# Sch_v3.net
KiCad netlist of a schematic drawn in EAGLE
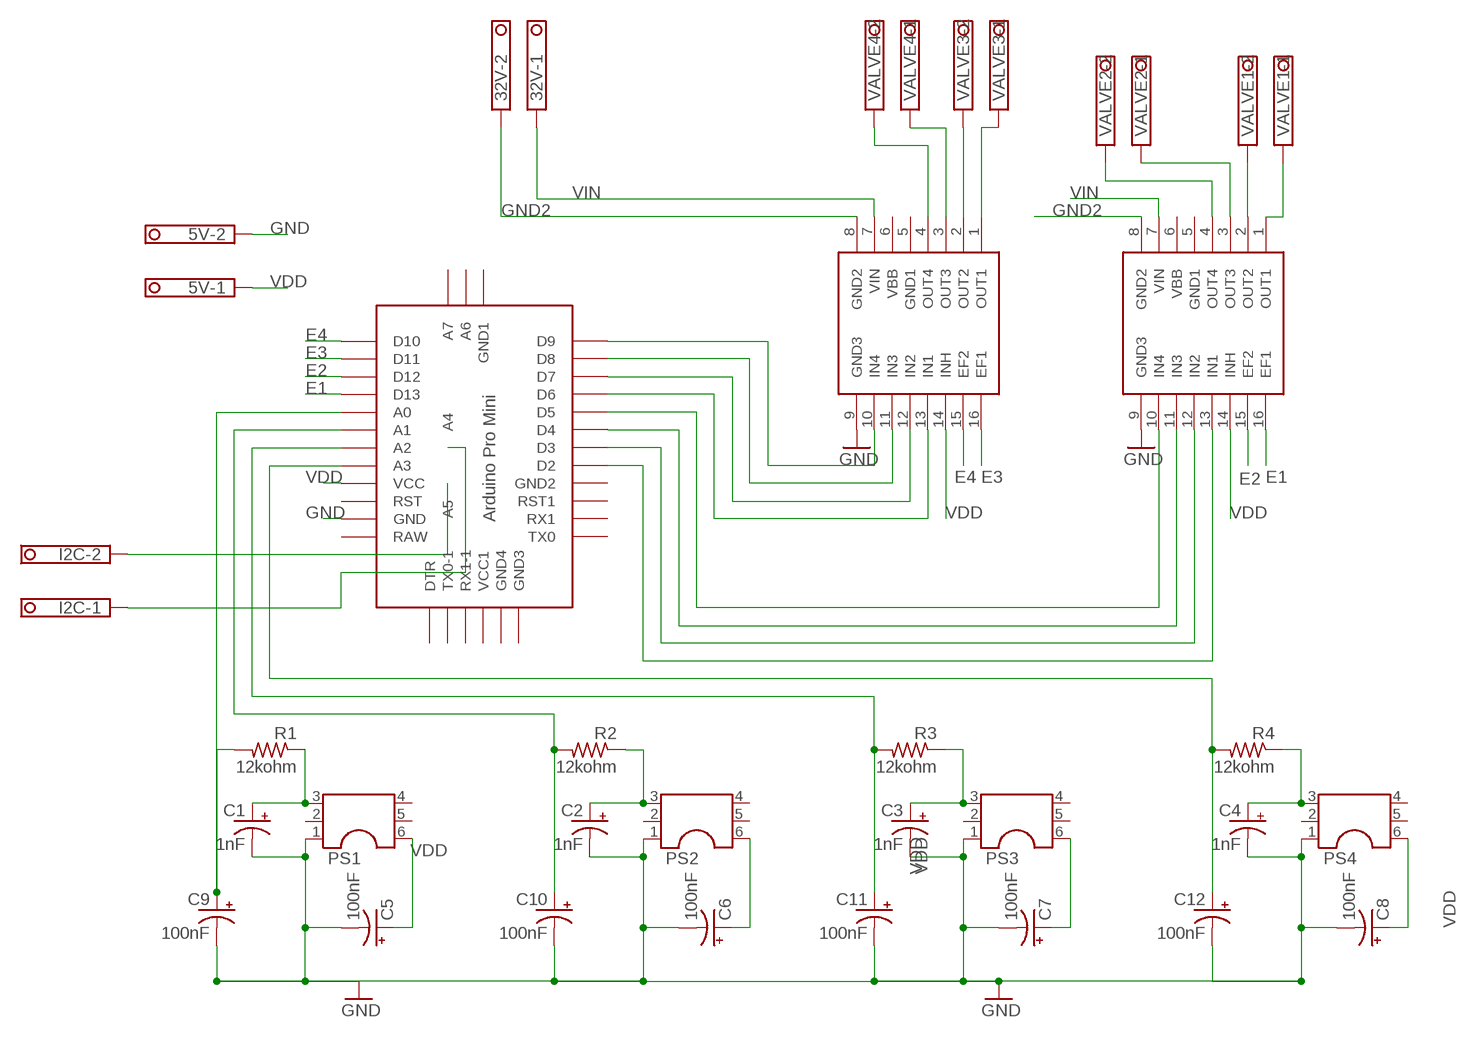
[diagram p0: schematic, sheet 1]

(export (version "E")
  (design (tool "Eeschema 10.0.6"))
  (components
    (comp (ref "5V")
      (value "1751248")
      (footprint "eagle-import:1751248")
      (libsource (lib "eagle-import") (part "1751248"))
    )
    (comp (ref "32V")
      (value "1751248")
      (footprint "eagle-import:1751248")
      (libsource (lib "eagle-import") (part "1751248"))
    )
    (comp (ref "C1")
      (value "1nF")
      (footprint "eagle-import:E2,5-5")
      (libsource (lib "eagle-import") (part "CPOL-USE2.5-5"))
    )
    (comp (ref "C2")
      (value "1nF")
      (footprint "eagle-import:E2,5-5")
      (libsource (lib "eagle-import") (part "CPOL-USE2.5-5"))
    )
    (comp (ref "C3")
      (value "1nF")
      (footprint "eagle-import:E2,5-5")
      (libsource (lib "eagle-import") (part "CPOL-USE2.5-5"))
    )
    (comp (ref "C4")
      (value "1nF")
      (footprint "eagle-import:E2,5-5")
      (libsource (lib "eagle-import") (part "CPOL-USE2.5-5"))
    )
    (comp (ref "C5")
      (value "100nF")
      (footprint "eagle-import:E2,5-5")
      (libsource (lib "eagle-import") (part "CPOL-USE2.5-5"))
    )
    (comp (ref "C6")
      (value "100nF")
      (footprint "eagle-import:E2,5-5")
      (libsource (lib "eagle-import") (part "CPOL-USE2.5-5"))
    )
    (comp (ref "C7")
      (value "100nF")
      (footprint "eagle-import:E2,5-5")
      (libsource (lib "eagle-import") (part "CPOL-USE2.5-5"))
    )
    (comp (ref "C8")
      (value "100nF")
      (footprint "eagle-import:E2,5-5")
      (libsource (lib "eagle-import") (part "CPOL-USE2.5-5"))
    )
    (comp (ref "C9")
      (value "100nF")
      (footprint "eagle-import:E2,5-5")
      (libsource (lib "eagle-import") (part "CPOL-USE2.5-5"))
    )
    (comp (ref "C10")
      (value "100nF")
      (footprint "eagle-import:E2,5-5")
      (libsource (lib "eagle-import") (part "CPOL-USE2.5-5"))
    )
    (comp (ref "C11")
      (value "100nF")
      (footprint "eagle-import:E2,5-5")
      (libsource (lib "eagle-import") (part "CPOL-USE2.5-5"))
    )
    (comp (ref "C12")
      (value "100nF")
      (footprint "eagle-import:E2,5-5")
      (libsource (lib "eagle-import") (part "CPOL-USE2.5-5"))
    )
    (comp (ref "I2C")
      (value "1751248")
      (footprint "eagle-import:1751248")
      (libsource (lib "eagle-import") (part "1751248"))
    )
    (comp (ref "PS1")
      (value "DIL6")
      (footprint "eagle-import:DIL06")
      (libsource (lib "eagle-import") (part "DIL6"))
    )
    (comp (ref "PS2")
      (value "DIL6")
      (footprint "eagle-import:DIL06")
      (libsource (lib "eagle-import") (part "DIL6"))
    )
    (comp (ref "PS3")
      (value "DIL6")
      (footprint "eagle-import:DIL06")
      (libsource (lib "eagle-import") (part "DIL6"))
    )
    (comp (ref "PS4")
      (value "DIL6")
      (footprint "eagle-import:DIL06")
      (libsource (lib "eagle-import") (part "DIL6"))
    )
    (comp (ref "R1")
      (value "12kohm")
      (footprint "eagle-import:0204_7")
      (libsource (lib "eagle-import") (part "R-US_0204/7"))
    )
    (comp (ref "R2")
      (value "12kohm")
      (footprint "eagle-import:0204_7")
      (libsource (lib "eagle-import") (part "R-US_0204/7"))
    )
    (comp (ref "R3")
      (value "12kohm")
      (footprint "eagle-import:0204_7")
      (libsource (lib "eagle-import") (part "R-US_0204/7"))
    )
    (comp (ref "R4")
      (value "12kohm")
      (footprint "eagle-import:0204_7")
      (libsource (lib "eagle-import") (part "R-US_0204/7"))
    )
    (comp (ref "U$1")
      (value "ABK-PRO-MINI")
      (footprint "eagle-import:ABK-PRO-MINI")
      (libsource (lib "eagle-import") (part "ABK-PRO-MINI"))
    )
    (comp (ref "U$2")
      (value "A4990")
      (footprint "eagle-import:A4990")
      (libsource (lib "eagle-import") (part "A4990"))
    )
    (comp (ref "U$3")
      (value "A4990")
      (footprint "eagle-import:A4990")
      (libsource (lib "eagle-import") (part "A4990"))
    )
    (comp (ref "VALVE1")
      (value "1751248")
      (footprint "eagle-import:1751248")
      (libsource (lib "eagle-import") (part "1751248"))
    )
    (comp (ref "VALVE2")
      (value "1751248")
      (footprint "eagle-import:1751248")
      (libsource (lib "eagle-import") (part "1751248"))
    )
    (comp (ref "VALVE3")
      (value "1751248")
      (footprint "eagle-import:1751248")
      (libsource (lib "eagle-import") (part "1751248"))
    )
    (comp (ref "VALVE4")
      (value "1751248")
      (footprint "eagle-import:1751248")
      (libsource (lib "eagle-import") (part "1751248"))
    )
  )
  (nets
    (net (code "1") (name "/E1") (class "Default")
      (node (ref "U$1") (pin "D13") (pinfunction "D13_D13") (pintype "bidirectional"))
      (node (ref "U$3") (pin "16") (pinfunction "EF1_16") (pintype "bidirectional"))
    )
    (net (code "2") (name "/E2") (class "Default")
      (node (ref "U$1") (pin "D12") (pinfunction "D12_D12") (pintype "bidirectional"))
      (node (ref "U$3") (pin "15") (pinfunction "EF2_15") (pintype "bidirectional"))
    )
    (net (code "3") (name "/E3") (class "Default")
      (node (ref "U$1") (pin "D11") (pinfunction "D11_D11") (pintype "bidirectional"))
      (node (ref "U$2") (pin "16") (pinfunction "EF1_16") (pintype "bidirectional"))
    )
    (net (code "4") (name "/E4") (class "Default")
      (node (ref "U$1") (pin "D10") (pinfunction "D10_D10") (pintype "bidirectional"))
      (node (ref "U$2") (pin "15") (pinfunction "EF2_15") (pintype "bidirectional"))
    )
    (net (code "5") (name "/GND2") (class "Default")
      (node (ref "32V") (pin "2") (pinfunction "K_2") (pintype "passive"))
      (node (ref "U$2") (pin "8") (pinfunction "GND2_8") (pintype "bidirectional"))
      (node (ref "U$3") (pin "8") (pinfunction "GND2_8") (pintype "bidirectional"))
    )
    (net (code "6") (name "/VDD") (class "Default")
      (node (ref "5V") (pin "1") (pinfunction "K_1") (pintype "passive"))
      (node (ref "C5") (pin "+") (pinfunction "+_+") (pintype "passive"))
      (node (ref "C6") (pin "+") (pinfunction "+_+") (pintype "passive"))
      (node (ref "C7") (pin "+") (pinfunction "+_+") (pintype "passive"))
      (node (ref "C8") (pin "+") (pinfunction "+_+") (pintype "passive"))
      (node (ref "PS1") (pin "6") (pinfunction "6_6") (pintype "passive"))
      (node (ref "PS2") (pin "6") (pinfunction "6_6") (pintype "passive"))
      (node (ref "PS3") (pin "6") (pinfunction "6_6") (pintype "passive"))
      (node (ref "PS4") (pin "6") (pinfunction "6_6") (pintype "passive"))
      (node (ref "U$1") (pin "VCC") (pinfunction "VCC_VCC") (pintype "bidirectional"))
      (node (ref "U$2") (pin "14") (pinfunction "INH_14") (pintype "bidirectional"))
      (node (ref "U$3") (pin "14") (pinfunction "INH_14") (pintype "bidirectional"))
    )
    (net (code "7") (name "/VIN") (class "Default")
      (node (ref "32V") (pin "1") (pinfunction "K_1") (pintype "passive"))
      (node (ref "U$2") (pin "7") (pinfunction "VIN_7") (pintype "bidirectional"))
      (node (ref "U$3") (pin "7") (pinfunction "VIN_7") (pintype "bidirectional"))
    )
    (net (code "8") (name "GND") (class "Default")
      (node (ref "5V") (pin "2") (pinfunction "K_2") (pintype "passive"))
      (node (ref "C1") (pin "-") (pinfunction "-_-") (pintype "passive"))
      (node (ref "C10") (pin "-") (pinfunction "-_-") (pintype "passive"))
      (node (ref "C11") (pin "-") (pinfunction "-_-") (pintype "passive"))
      (node (ref "C12") (pin "-") (pinfunction "-_-") (pintype "passive"))
      (node (ref "C2") (pin "-") (pinfunction "-_-") (pintype "passive"))
      (node (ref "C3") (pin "-") (pinfunction "-_-") (pintype "passive"))
      (node (ref "C4") (pin "-") (pinfunction "-_-") (pintype "passive"))
      (node (ref "C5") (pin "-") (pinfunction "-_-") (pintype "passive"))
      (node (ref "C6") (pin "-") (pinfunction "-_-") (pintype "passive"))
      (node (ref "C7") (pin "-") (pinfunction "-_-") (pintype "passive"))
      (node (ref "C8") (pin "-") (pinfunction "-_-") (pintype "passive"))
      (node (ref "C9") (pin "-") (pinfunction "-_-") (pintype "passive"))
      (node (ref "PS1") (pin "1") (pinfunction "1_1") (pintype "passive"))
      (node (ref "PS2") (pin "1") (pinfunction "1_1") (pintype "passive"))
      (node (ref "PS3") (pin "1") (pinfunction "1_1") (pintype "passive"))
      (node (ref "PS4") (pin "1") (pinfunction "1_1") (pintype "passive"))
      (node (ref "U$1") (pin "GND") (pinfunction "GND_GND") (pintype "bidirectional"))
      (node (ref "U$2") (pin "9") (pinfunction "GND3_9") (pintype "bidirectional"))
      (node (ref "U$3") (pin "9") (pinfunction "GND3_9") (pintype "bidirectional"))
    )
    (net (code "9") (name "Net-(C1-Pad+)") (class "Default")
      (node (ref "C1") (pin "+") (pinfunction "+_+") (pintype "passive"))
      (node (ref "PS1") (pin "3") (pinfunction "3_3") (pintype "passive"))
      (node (ref "R1") (pin "1") (pinfunction "1_1") (pintype "passive"))
    )
    (net (code "10") (name "Net-(C2-Pad+)") (class "Default")
      (node (ref "C2") (pin "+") (pinfunction "+_+") (pintype "passive"))
      (node (ref "PS2") (pin "3") (pinfunction "3_3") (pintype "passive"))
      (node (ref "R2") (pin "1") (pinfunction "1_1") (pintype "passive"))
    )
    (net (code "11") (name "Net-(C3-Pad+)") (class "Default")
      (node (ref "C3") (pin "+") (pinfunction "+_+") (pintype "passive"))
      (node (ref "PS3") (pin "3") (pinfunction "3_3") (pintype "passive"))
      (node (ref "R3") (pin "1") (pinfunction "1_1") (pintype "passive"))
    )
    (net (code "12") (name "Net-(C4-Pad+)") (class "Default")
      (node (ref "C4") (pin "+") (pinfunction "+_+") (pintype "passive"))
      (node (ref "PS4") (pin "3") (pinfunction "3_3") (pintype "passive"))
      (node (ref "R4") (pin "1") (pinfunction "1_1") (pintype "passive"))
    )
    (net (code "13") (name "Net-(C9-Pad+)") (class "Default")
      (node (ref "C9") (pin "+") (pinfunction "+_+") (pintype "passive"))
      (node (ref "R1") (pin "2") (pinfunction "2_2") (pintype "passive"))
      (node (ref "U$1") (pin "A0") (pinfunction "A0_A0") (pintype "bidirectional"))
    )
    (net (code "14") (name "Net-(C10-Pad+)") (class "Default")
      (node (ref "C10") (pin "+") (pinfunction "+_+") (pintype "passive"))
      (node (ref "R2") (pin "2") (pinfunction "2_2") (pintype "passive"))
      (node (ref "U$1") (pin "A1") (pinfunction "A1_A1") (pintype "bidirectional"))
    )
    (net (code "15") (name "Net-(C11-Pad+)") (class "Default")
      (node (ref "C11") (pin "+") (pinfunction "+_+") (pintype "passive"))
      (node (ref "R3") (pin "2") (pinfunction "2_2") (pintype "passive"))
      (node (ref "U$1") (pin "A2") (pinfunction "A2_A2") (pintype "bidirectional"))
    )
    (net (code "16") (name "Net-(C12-Pad+)") (class "Default")
      (node (ref "C12") (pin "+") (pinfunction "+_+") (pintype "passive"))
      (node (ref "R4") (pin "2") (pinfunction "2_2") (pintype "passive"))
      (node (ref "U$1") (pin "A3") (pinfunction "A3_A3") (pintype "bidirectional"))
    )
    (net (code "17") (name "Net-(I2CA-K)") (class "Default")
      (node (ref "I2C") (pin "1") (pinfunction "K_1") (pintype "passive"))
      (node (ref "U$1") (pin "A4") (pinfunction "A4_A4") (pintype "bidirectional"))
    )
    (net (code "18") (name "Net-(I2CB-K)") (class "Default")
      (node (ref "I2C") (pin "2") (pinfunction "K_2") (pintype "passive"))
      (node (ref "U$1") (pin "A5") (pinfunction "A5_A5") (pintype "bidirectional"))
    )
    (net (code "19") (name "Net-(U$2-IN1)") (class "Default")
      (node (ref "U$1") (pin "D6") (pinfunction "D6_D6") (pintype "bidirectional"))
      (node (ref "U$2") (pin "13") (pinfunction "IN1_13") (pintype "bidirectional"))
    )
    (net (code "20") (name "Net-(U$2-IN2)") (class "Default")
      (node (ref "U$1") (pin "D7") (pinfunction "D7_D7") (pintype "bidirectional"))
      (node (ref "U$2") (pin "12") (pinfunction "IN2_12") (pintype "bidirectional"))
    )
    (net (code "21") (name "Net-(U$2-IN3)") (class "Default")
      (node (ref "U$1") (pin "D8") (pinfunction "D8_D8") (pintype "bidirectional"))
      (node (ref "U$2") (pin "11") (pinfunction "IN3_11") (pintype "bidirectional"))
    )
    (net (code "22") (name "Net-(U$2-IN4)") (class "Default")
      (node (ref "U$1") (pin "D9") (pinfunction "D9_D9") (pintype "bidirectional"))
      (node (ref "U$2") (pin "10") (pinfunction "IN4_10") (pintype "bidirectional"))
    )
    (net (code "23") (name "Net-(U$2-OUT1)") (class "Default")
      (node (ref "U$2") (pin "1") (pinfunction "OUT1_1") (pintype "bidirectional"))
      (node (ref "VALVE3") (pin "1") (pinfunction "K_1") (pintype "passive"))
    )
    (net (code "24") (name "Net-(U$2-OUT2)") (class "Default")
      (node (ref "U$2") (pin "2") (pinfunction "OUT2_2") (pintype "bidirectional"))
      (node (ref "VALVE3") (pin "2") (pinfunction "K_2") (pintype "passive"))
    )
    (net (code "25") (name "Net-(U$2-OUT3)") (class "Default")
      (node (ref "U$2") (pin "3") (pinfunction "OUT3_3") (pintype "bidirectional"))
      (node (ref "VALVE4") (pin "1") (pinfunction "K_1") (pintype "passive"))
    )
    (net (code "26") (name "Net-(U$2-OUT4)") (class "Default")
      (node (ref "U$2") (pin "4") (pinfunction "OUT4_4") (pintype "bidirectional"))
      (node (ref "VALVE4") (pin "2") (pinfunction "K_2") (pintype "passive"))
    )
    (net (code "27") (name "Net-(U$3-IN1)") (class "Default")
      (node (ref "U$1") (pin "D2") (pinfunction "D2_D2") (pintype "bidirectional"))
      (node (ref "U$3") (pin "13") (pinfunction "IN1_13") (pintype "bidirectional"))
    )
    (net (code "28") (name "Net-(U$3-IN2)") (class "Default")
      (node (ref "U$1") (pin "D3") (pinfunction "D3_D3") (pintype "bidirectional"))
      (node (ref "U$3") (pin "12") (pinfunction "IN2_12") (pintype "bidirectional"))
    )
    (net (code "29") (name "Net-(U$3-IN3)") (class "Default")
      (node (ref "U$1") (pin "D4") (pinfunction "D4_D4") (pintype "bidirectional"))
      (node (ref "U$3") (pin "11") (pinfunction "IN3_11") (pintype "bidirectional"))
    )
    (net (code "30") (name "Net-(U$3-IN4)") (class "Default")
      (node (ref "U$1") (pin "D5") (pinfunction "D5_D5") (pintype "bidirectional"))
      (node (ref "U$3") (pin "10") (pinfunction "IN4_10") (pintype "bidirectional"))
    )
    (net (code "31") (name "Net-(U$3-OUT1)") (class "Default")
      (node (ref "U$3") (pin "1") (pinfunction "OUT1_1") (pintype "bidirectional"))
      (node (ref "VALVE1") (pin "1") (pinfunction "K_1") (pintype "passive"))
    )
    (net (code "32") (name "Net-(U$3-OUT2)") (class "Default")
      (node (ref "U$3") (pin "2") (pinfunction "OUT2_2") (pintype "bidirectional"))
      (node (ref "VALVE1") (pin "2") (pinfunction "K_2") (pintype "passive"))
    )
    (net (code "33") (name "Net-(U$3-OUT3)") (class "Default")
      (node (ref "U$3") (pin "3") (pinfunction "OUT3_3") (pintype "bidirectional"))
      (node (ref "VALVE2") (pin "1") (pinfunction "K_1") (pintype "passive"))
    )
    (net (code "34") (name "Net-(U$3-OUT4)") (class "Default")
      (node (ref "U$3") (pin "4") (pinfunction "OUT4_4") (pintype "bidirectional"))
      (node (ref "VALVE2") (pin "2") (pinfunction "K_2") (pintype "passive"))
    )
    (net (code "35") (name "unconnected-(PS1-Pad2)") (class "Default")
      (node (ref "PS1") (pin "2") (pinfunction "2_2") (pintype "passive"))
    )
    (net (code "36") (name "unconnected-(PS1-Pad4)") (class "Default")
      (node (ref "PS1") (pin "4") (pinfunction "4_4") (pintype "passive"))
    )
    (net (code "37") (name "unconnected-(PS1-Pad5)") (class "Default")
      (node (ref "PS1") (pin "5") (pinfunction "5_5") (pintype "passive"))
    )
    (net (code "38") (name "unconnected-(PS2-Pad2)") (class "Default")
      (node (ref "PS2") (pin "2") (pinfunction "2_2") (pintype "passive"))
    )
    (net (code "39") (name "unconnected-(PS2-Pad4)") (class "Default")
      (node (ref "PS2") (pin "4") (pinfunction "4_4") (pintype "passive"))
    )
    (net (code "40") (name "unconnected-(PS2-Pad5)") (class "Default")
      (node (ref "PS2") (pin "5") (pinfunction "5_5") (pintype "passive"))
    )
    (net (code "41") (name "unconnected-(PS3-Pad2)") (class "Default")
      (node (ref "PS3") (pin "2") (pinfunction "2_2") (pintype "passive"))
    )
    (net (code "42") (name "unconnected-(PS3-Pad4)") (class "Default")
      (node (ref "PS3") (pin "4") (pinfunction "4_4") (pintype "passive"))
    )
    (net (code "43") (name "unconnected-(PS3-Pad5)") (class "Default")
      (node (ref "PS3") (pin "5") (pinfunction "5_5") (pintype "passive"))
    )
    (net (code "44") (name "unconnected-(PS4-Pad2)") (class "Default")
      (node (ref "PS4") (pin "2") (pinfunction "2_2") (pintype "passive"))
    )
    (net (code "45") (name "unconnected-(PS4-Pad4)") (class "Default")
      (node (ref "PS4") (pin "4") (pinfunction "4_4") (pintype "passive"))
    )
    (net (code "46") (name "unconnected-(PS4-Pad5)") (class "Default")
      (node (ref "PS4") (pin "5") (pinfunction "5_5") (pintype "passive"))
    )
    (net (code "47") (name "unconnected-(U$1-GND1-PadGND4)") (class "Default")
      (node (ref "U$1") (pin "GND4") (pinfunction "GND1_GND4") (pintype "bidirectional"))
    )
    (net (code "48") (name "unconnected-(U$1-GND2-PadGND1)") (class "Default")
      (node (ref "U$1") (pin "GND1") (pinfunction "GND2_GND1") (pintype "bidirectional"))
    )
    (net (code "49") (name "unconnected-(U$1-GND3-PadGND2)") (class "Default")
      (node (ref "U$1") (pin "GND2") (pinfunction "GND3_GND2") (pintype "bidirectional"))
    )
    (net (code "50") (name "unconnected-(U$1-GND4-PadGND3)") (class "Default")
      (node (ref "U$1") (pin "GND3") (pinfunction "GND4_GND3") (pintype "bidirectional"))
    )
    (net (code "51") (name "unconnected-(U$1-PadA6)") (class "Default")
      (node (ref "U$1") (pin "A6") (pinfunction "A6_A6") (pintype "bidirectional"))
    )
    (net (code "52") (name "unconnected-(U$1-PadA7)") (class "Default")
      (node (ref "U$1") (pin "A7") (pinfunction "A7_A7") (pintype "bidirectional"))
    )
    (net (code "53") (name "unconnected-(U$1-PadDTR)") (class "Default")
      (node (ref "U$1") (pin "DTR") (pinfunction "DTR_DTR") (pintype "bidirectional"))
    )
    (net (code "54") (name "unconnected-(U$1-PadRAW)") (class "Default")
      (node (ref "U$1") (pin "RAW") (pinfunction "RAW_RAW") (pintype "bidirectional"))
    )
    (net (code "55") (name "unconnected-(U$1-PadRST)") (class "Default")
      (node (ref "U$1") (pin "RST") (pinfunction "RST_RST") (pintype "bidirectional"))
    )
    (net (code "56") (name "unconnected-(U$1-PadRST1)") (class "Default")
      (node (ref "U$1") (pin "RST1") (pinfunction "RST1_RST1") (pintype "bidirectional"))
    )
    (net (code "57") (name "unconnected-(U$1-PadRX1)") (class "Default")
      (node (ref "U$1") (pin "RX1") (pinfunction "RX1_RX1") (pintype "bidirectional"))
    )
    (net (code "58") (name "unconnected-(U$1-PadRX1-1)") (class "Default")
      (node (ref "U$1") (pin "RX1-1") (pinfunction "RX1-1_RX1-1") (pintype "bidirectional"))
    )
    (net (code "59") (name "unconnected-(U$1-PadTX0)") (class "Default")
      (node (ref "U$1") (pin "TX0") (pinfunction "TX0_TX0") (pintype "bidirectional"))
    )
    (net (code "60") (name "unconnected-(U$1-PadTX0-1)") (class "Default")
      (node (ref "U$1") (pin "TX0-1") (pinfunction "TX0-1_TX0-1") (pintype "bidirectional"))
    )
    (net (code "61") (name "unconnected-(U$1-PadVCC1)") (class "Default")
      (node (ref "U$1") (pin "VCC1") (pinfunction "VCC1_VCC1") (pintype "bidirectional"))
    )
    (net (code "62") (name "unconnected-(U$2-GND1-Pad5)") (class "Default")
      (node (ref "U$2") (pin "5") (pinfunction "GND1_5") (pintype "bidirectional"))
    )
    (net (code "63") (name "unconnected-(U$2-VBB-Pad6)") (class "Default")
      (node (ref "U$2") (pin "6") (pinfunction "VBB_6") (pintype "bidirectional"))
    )
    (net (code "64") (name "unconnected-(U$3-GND1-Pad5)") (class "Default")
      (node (ref "U$3") (pin "5") (pinfunction "GND1_5") (pintype "bidirectional"))
    )
    (net (code "65") (name "unconnected-(U$3-VBB-Pad6)") (class "Default")
      (node (ref "U$3") (pin "6") (pinfunction "VBB_6") (pintype "bidirectional"))
    )
  )
)
